# CSI.net
KiCad netlist of a schematic drawn in Altium Designer
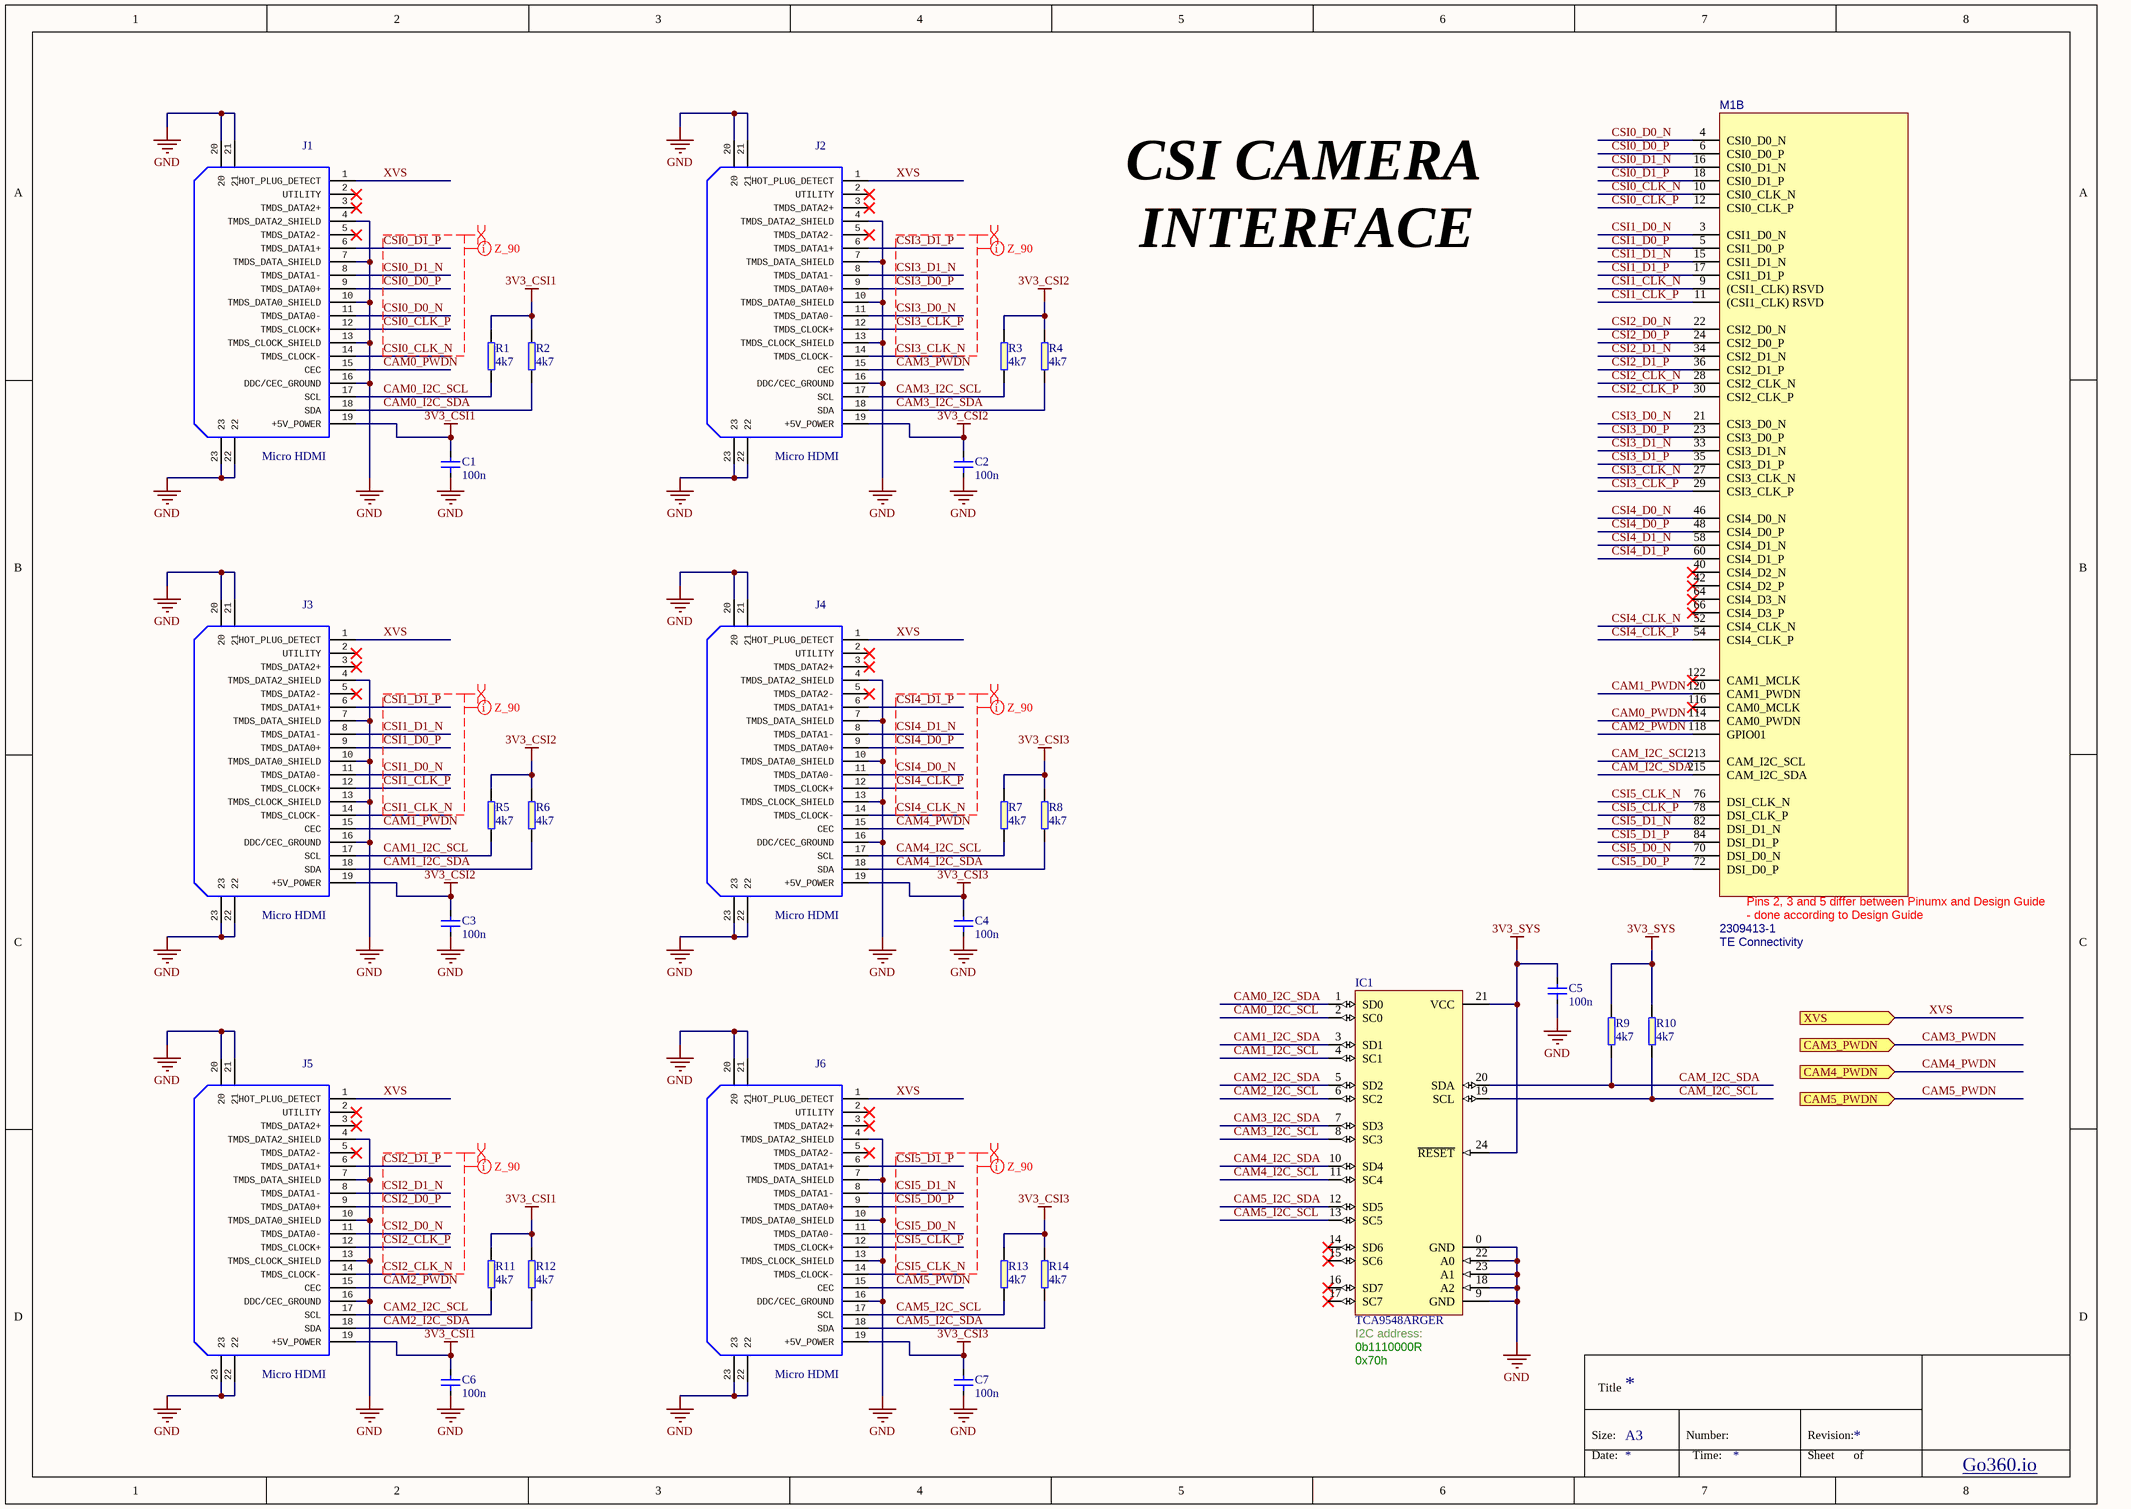
[diagram p0: CSI.SchDoc]

(export (version "E")
  (design (tool "Eeschema 10.0.6"))
  (components
    (comp (ref "C1")
      (value "100n")
      (footprint "C0402")
      (description "MLCC SMT Capacitor 100n 0402")
      (fields (field (name "PARTNUMBER") "C_100n_0402") (field (name "MANUFACTURER") "TDK"))
      (libsource (lib "jetson-nano-baseboard") (part "C_100n_0402"))
    )
    (comp (ref "C2")
      (value "100n")
      (footprint "C0402")
      (description "MLCC SMT Capacitor 100n 0402")
      (fields (field (name "PARTNUMBER") "C_100n_0402") (field (name "MANUFACTURER") "TDK"))
      (libsource (lib "jetson-nano-baseboard") (part "C_100n_0402"))
    )
    (comp (ref "C3")
      (value "100n")
      (footprint "C0402")
      (description "MLCC SMT Capacitor 100n 0402")
      (fields (field (name "PARTNUMBER") "C_100n_0402") (field (name "MANUFACTURER") "TDK"))
      (libsource (lib "jetson-nano-baseboard") (part "C_100n_0402"))
    )
    (comp (ref "C4")
      (value "100n")
      (footprint "C0402")
      (description "MLCC SMT Capacitor 100n 0402")
      (fields (field (name "PARTNUMBER") "C_100n_0402") (field (name "MANUFACTURER") "TDK"))
      (libsource (lib "jetson-nano-baseboard") (part "C_100n_0402"))
    )
    (comp (ref "C5")
      (value "100n")
      (footprint "C0402")
      (description "MLCC SMT Capacitor 100n 0402")
      (fields (field (name "PARTNUMBER") "C_100n_0402") (field (name "MANUFACTURER") "TDK"))
      (libsource (lib "jetson-nano-baseboard") (part "C_100n_0402"))
    )
    (comp (ref "C6")
      (value "100n")
      (footprint "C0402")
      (description "MLCC SMT Capacitor 100n 0402")
      (fields (field (name "PARTNUMBER") "C_100n_0402") (field (name "MANUFACTURER") "TDK"))
      (libsource (lib "jetson-nano-baseboard") (part "C_100n_0402"))
    )
    (comp (ref "C7")
      (value "100n")
      (footprint "C0402")
      (description "MLCC SMT Capacitor 100n 0402")
      (fields (field (name "PARTNUMBER") "C_100n_0402") (field (name "MANUFACTURER") "TDK"))
      (libsource (lib "jetson-nano-baseboard") (part "C_100n_0402"))
    )
    (comp (ref "IC1")
      (value "TCA9548ARGER")
      (footprint "VQFN-24")
      (description "TCA9548ARGER  I2C SWITCH W/ RESET, 8-CH, VQFN-24")
      (fields (field (name "MANUFACTURER") "TEXAS INSTRUMENTS"))
      (libsource (lib "jetson-nano-baseboard") (part "TCA9548A"))
    )
    (comp (ref "J1")
      (value "Micro HDMI")
      (footprint "HDMI-0467650301")
      (libsource (lib "jetson-nano-baseboard") (part "HDMI-0467650301"))
    )
    (comp (ref "J2")
      (value "Micro HDMI")
      (footprint "HDMI-0467650301")
      (libsource (lib "jetson-nano-baseboard") (part "HDMI-0467650301"))
    )
    (comp (ref "J3")
      (value "Micro HDMI")
      (footprint "HDMI-0467650301")
      (libsource (lib "jetson-nano-baseboard") (part "HDMI-0467650301"))
    )
    (comp (ref "J4")
      (value "Micro HDMI")
      (footprint "HDMI-0467650301")
      (libsource (lib "jetson-nano-baseboard") (part "HDMI-0467650301"))
    )
    (comp (ref "J5")
      (value "Micro HDMI")
      (footprint "HDMI-0467650301")
      (libsource (lib "jetson-nano-baseboard") (part "HDMI-0467650301"))
    )
    (comp (ref "J6")
      (value "Micro HDMI")
      (footprint "HDMI-0467650301")
      (libsource (lib "jetson-nano-baseboard") (part "HDMI-0467650301"))
    )
    (comp (ref "M1")
      (value "2309413-1")
      (footprint "jetson-nano-connector")
      (fields (field (name "PARTSYMBOL") "2309413-1") (field (name "MANUFACTURER") "TE Connectivity"))
      (libsource (lib "jetson-nano-baseboard") (part "jetson-nano-new-release"))
    )
    (comp (ref "R1")
      (value "4k7")
      (footprint "R0402")
      (description "RES, 4k7, 0402")
      (fields (field (name "PARTNUMBER") "R_4k7_0402") (field (name "MANUFACTURER") "Panasonic"))
      (libsource (lib "jetson-nano-baseboard") (part "R_4k7_0402"))
    )
    (comp (ref "R2")
      (value "4k7")
      (footprint "R0402")
      (description "RES, 4k7, 0402")
      (fields (field (name "PARTNUMBER") "R_4k7_0402") (field (name "MANUFACTURER") "Panasonic"))
      (libsource (lib "jetson-nano-baseboard") (part "R_4k7_0402"))
    )
    (comp (ref "R3")
      (value "4k7")
      (footprint "R0402")
      (description "RES, 4k7, 0402")
      (fields (field (name "PARTNUMBER") "R_4k7_0402") (field (name "MANUFACTURER") "Panasonic"))
      (libsource (lib "jetson-nano-baseboard") (part "R_4k7_0402"))
    )
    (comp (ref "R4")
      (value "4k7")
      (footprint "R0402")
      (description "RES, 4k7, 0402")
      (fields (field (name "PARTNUMBER") "R_4k7_0402") (field (name "MANUFACTURER") "Panasonic"))
      (libsource (lib "jetson-nano-baseboard") (part "R_4k7_0402"))
    )
    (comp (ref "R5")
      (value "4k7")
      (footprint "R0402")
      (description "RES, 4k7, 0402")
      (fields (field (name "PARTNUMBER") "R_4k7_0402") (field (name "MANUFACTURER") "Panasonic"))
      (libsource (lib "jetson-nano-baseboard") (part "R_4k7_0402"))
    )
    (comp (ref "R6")
      (value "4k7")
      (footprint "R0402")
      (description "RES, 4k7, 0402")
      (fields (field (name "PARTNUMBER") "R_4k7_0402") (field (name "MANUFACTURER") "Panasonic"))
      (libsource (lib "jetson-nano-baseboard") (part "R_4k7_0402"))
    )
    (comp (ref "R7")
      (value "4k7")
      (footprint "R0402")
      (description "RES, 4k7, 0402")
      (fields (field (name "PARTNUMBER") "R_4k7_0402") (field (name "MANUFACTURER") "Panasonic"))
      (libsource (lib "jetson-nano-baseboard") (part "R_4k7_0402"))
    )
    (comp (ref "R8")
      (value "4k7")
      (footprint "R0402")
      (description "RES, 4k7, 0402")
      (fields (field (name "PARTNUMBER") "R_4k7_0402") (field (name "MANUFACTURER") "Panasonic"))
      (libsource (lib "jetson-nano-baseboard") (part "R_4k7_0402"))
    )
    (comp (ref "R9")
      (value "4k7")
      (footprint "R0402")
      (description "RES, 4k7, 0402")
      (fields (field (name "PARTNUMBER") "R_4k7_0402") (field (name "MANUFACTURER") "Panasonic"))
      (libsource (lib "jetson-nano-baseboard") (part "R_4k7_0402"))
    )
    (comp (ref "R10")
      (value "4k7")
      (footprint "R0402")
      (description "RES, 4k7, 0402")
      (fields (field (name "PARTNUMBER") "R_4k7_0402") (field (name "MANUFACTURER") "Panasonic"))
      (libsource (lib "jetson-nano-baseboard") (part "R_4k7_0402"))
    )
    (comp (ref "R11")
      (value "4k7")
      (footprint "R0402")
      (description "RES, 4k7, 0402")
      (fields (field (name "PARTNUMBER") "R_4k7_0402") (field (name "MANUFACTURER") "Panasonic"))
      (libsource (lib "jetson-nano-baseboard") (part "R_4k7_0402"))
    )
    (comp (ref "R12")
      (value "4k7")
      (footprint "R0402")
      (description "RES, 4k7, 0402")
      (fields (field (name "PARTNUMBER") "R_4k7_0402") (field (name "MANUFACTURER") "Panasonic"))
      (libsource (lib "jetson-nano-baseboard") (part "R_4k7_0402"))
    )
    (comp (ref "R13")
      (value "4k7")
      (footprint "R0402")
      (description "RES, 4k7, 0402")
      (fields (field (name "PARTNUMBER") "R_4k7_0402") (field (name "MANUFACTURER") "Panasonic"))
      (libsource (lib "jetson-nano-baseboard") (part "R_4k7_0402"))
    )
    (comp (ref "R14")
      (value "4k7")
      (footprint "R0402")
      (description "RES, 4k7, 0402")
      (fields (field (name "PARTNUMBER") "R_4k7_0402") (field (name "MANUFACTURER") "Panasonic"))
      (libsource (lib "jetson-nano-baseboard") (part "R_4k7_0402"))
    )
  )
  (nets
    (net (code "1") (name "/CAM0_I2C_SCL") (class "Default")
      (node (ref "IC1") (pin "2") (pinfunction "SC0_2") (pintype "bidirectional"))
      (node (ref "J1") (pin "17") (pinfunction "SCL_17") (pintype "passive"))
      (node (ref "R1") (pin "1") (pintype "passive"))
    )
    (net (code "2") (name "/CAM0_I2C_SDA") (class "Default")
      (node (ref "IC1") (pin "1") (pinfunction "SD0_1") (pintype "bidirectional"))
      (node (ref "J1") (pin "18") (pinfunction "SDA_18") (pintype "passive"))
      (node (ref "R2") (pin "1") (pintype "passive"))
    )
    (net (code "3") (name "/CAM0_PWDN") (class "Default")
      (node (ref "J1") (pin "15") (pinfunction "CEC_15") (pintype "passive"))
      (node (ref "M1") (pin "114") (pinfunction "CAM0_PWDN_114") (pintype "passive"))
    )
    (net (code "4") (name "/CAM1_I2C_SCL") (class "Default")
      (node (ref "IC1") (pin "4") (pinfunction "SC1_4") (pintype "bidirectional"))
      (node (ref "J3") (pin "17") (pinfunction "SCL_17") (pintype "passive"))
      (node (ref "R5") (pin "1") (pintype "passive"))
    )
    (net (code "5") (name "/CAM1_I2C_SDA") (class "Default")
      (node (ref "IC1") (pin "3") (pinfunction "SD1_3") (pintype "bidirectional"))
      (node (ref "J3") (pin "18") (pinfunction "SDA_18") (pintype "passive"))
      (node (ref "R6") (pin "1") (pintype "passive"))
    )
    (net (code "6") (name "/CAM1_PWDN") (class "Default")
      (node (ref "J3") (pin "15") (pinfunction "CEC_15") (pintype "passive"))
      (node (ref "M1") (pin "120") (pinfunction "CAM1_PWDN_120") (pintype "passive"))
    )
    (net (code "7") (name "/CAM2_I2C_SCL") (class "Default")
      (node (ref "IC1") (pin "6") (pinfunction "SC2_6") (pintype "bidirectional"))
      (node (ref "J5") (pin "17") (pinfunction "SCL_17") (pintype "passive"))
      (node (ref "R11") (pin "1") (pintype "passive"))
    )
    (net (code "8") (name "/CAM2_I2C_SDA") (class "Default")
      (node (ref "IC1") (pin "5") (pinfunction "SD2_5") (pintype "bidirectional"))
      (node (ref "J5") (pin "18") (pinfunction "SDA_18") (pintype "passive"))
      (node (ref "R12") (pin "1") (pintype "passive"))
    )
    (net (code "9") (name "/CAM2_PWDN") (class "Default")
      (node (ref "J5") (pin "15") (pinfunction "CEC_15") (pintype "passive"))
      (node (ref "M1") (pin "118") (pinfunction "GPIO01_118") (pintype "passive"))
    )
    (net (code "10") (name "/CAM3_I2C_SCL") (class "Default")
      (node (ref "IC1") (pin "8") (pinfunction "SC3_8") (pintype "bidirectional"))
      (node (ref "J2") (pin "17") (pinfunction "SCL_17") (pintype "passive"))
      (node (ref "R3") (pin "1") (pintype "passive"))
    )
    (net (code "11") (name "/CAM3_I2C_SDA") (class "Default")
      (node (ref "IC1") (pin "7") (pinfunction "SD3_7") (pintype "bidirectional"))
      (node (ref "J2") (pin "18") (pinfunction "SDA_18") (pintype "passive"))
      (node (ref "R4") (pin "1") (pintype "passive"))
    )
    (net (code "12") (name "/CAM3_PWDN") (class "Default")
      (node (ref "J2") (pin "15") (pinfunction "CEC_15") (pintype "passive"))
    )
    (net (code "13") (name "/CAM4_I2C_SCL") (class "Default")
      (node (ref "IC1") (pin "11") (pinfunction "SC4_11") (pintype "bidirectional"))
      (node (ref "J4") (pin "17") (pinfunction "SCL_17") (pintype "passive"))
      (node (ref "R7") (pin "1") (pintype "passive"))
    )
    (net (code "14") (name "/CAM4_I2C_SDA") (class "Default")
      (node (ref "IC1") (pin "10") (pinfunction "SD4_10") (pintype "bidirectional"))
      (node (ref "J4") (pin "18") (pinfunction "SDA_18") (pintype "passive"))
      (node (ref "R8") (pin "1") (pintype "passive"))
    )
    (net (code "15") (name "/CAM4_PWDN") (class "Default")
      (node (ref "J4") (pin "15") (pinfunction "CEC_15") (pintype "passive"))
    )
    (net (code "16") (name "/CAM5_I2C_SCL") (class "Default")
      (node (ref "IC1") (pin "13") (pinfunction "SC5_13") (pintype "bidirectional"))
      (node (ref "J6") (pin "17") (pinfunction "SCL_17") (pintype "passive"))
      (node (ref "R13") (pin "1") (pintype "passive"))
    )
    (net (code "17") (name "/CAM5_I2C_SDA") (class "Default")
      (node (ref "IC1") (pin "12") (pinfunction "SD5_12") (pintype "bidirectional"))
      (node (ref "J6") (pin "18") (pinfunction "SDA_18") (pintype "passive"))
      (node (ref "R14") (pin "1") (pintype "passive"))
    )
    (net (code "18") (name "/CAM5_PWDN") (class "Default")
      (node (ref "J6") (pin "15") (pinfunction "CEC_15") (pintype "passive"))
    )
    (net (code "19") (name "/CAM_I2C_SCL") (class "Default")
      (node (ref "IC1") (pin "19") (pinfunction "SCL_19") (pintype "bidirectional"))
      (node (ref "M1") (pin "213") (pinfunction "CAM_I2C_SCL_213") (pintype "passive"))
      (node (ref "R10") (pin "1") (pintype "passive"))
    )
    (net (code "20") (name "/CAM_I2C_SDA") (class "Default")
      (node (ref "IC1") (pin "20") (pinfunction "SDA_20") (pintype "bidirectional"))
      (node (ref "M1") (pin "215") (pinfunction "CAM_I2C_SDA_215") (pintype "passive"))
      (node (ref "R9") (pin "1") (pintype "passive"))
    )
    (net (code "21") (name "/CSI0_CLK_N") (class "Default")
      (node (ref "J1") (pin "14") (pinfunction "TMDS_CLOCK-_14") (pintype "passive"))
      (node (ref "M1") (pin "10") (pinfunction "CSI0_CLK_N_10") (pintype "passive"))
    )
    (net (code "22") (name "/CSI0_CLK_P") (class "Default")
      (node (ref "J1") (pin "12") (pinfunction "TMDS_CLOCK+_12") (pintype "passive"))
      (node (ref "M1") (pin "12") (pinfunction "CSI0_CLK_P_12") (pintype "passive"))
    )
    (net (code "23") (name "/CSI0_D0_N") (class "Default")
      (node (ref "J1") (pin "11") (pinfunction "TMDS_DATA0-_11") (pintype "passive"))
      (node (ref "M1") (pin "4") (pinfunction "CSI0_D0_N_4") (pintype "passive"))
    )
    (net (code "24") (name "/CSI0_D0_P") (class "Default")
      (node (ref "J1") (pin "9") (pinfunction "TMDS_DATA0+_9") (pintype "passive"))
      (node (ref "M1") (pin "6") (pinfunction "CSI0_D0_P_6") (pintype "passive"))
    )
    (net (code "25") (name "/CSI0_D1_N") (class "Default")
      (node (ref "J1") (pin "8") (pinfunction "TMDS_DATA1-_8") (pintype "passive"))
      (node (ref "M1") (pin "16") (pinfunction "CSI0_D1_N_16") (pintype "passive"))
    )
    (net (code "26") (name "/CSI0_D1_P") (class "Default")
      (node (ref "J1") (pin "6") (pinfunction "TMDS_DATA1+_6") (pintype "passive"))
      (node (ref "M1") (pin "18") (pinfunction "CSI0_D1_P_18") (pintype "passive"))
    )
    (net (code "27") (name "/CSI1_CLK_N") (class "Default")
      (node (ref "J3") (pin "14") (pinfunction "TMDS_CLOCK-_14") (pintype "passive"))
      (node (ref "M1") (pin "9") (pinfunction "(CSI1_CLK)_RSVD_9") (pintype "passive"))
    )
    (net (code "28") (name "/CSI1_CLK_P") (class "Default")
      (node (ref "J3") (pin "12") (pinfunction "TMDS_CLOCK+_12") (pintype "passive"))
      (node (ref "M1") (pin "11") (pinfunction "(CSI1_CLK)_RSVD_11") (pintype "passive"))
    )
    (net (code "29") (name "/CSI1_D0_N") (class "Default")
      (node (ref "J3") (pin "11") (pinfunction "TMDS_DATA0-_11") (pintype "passive"))
      (node (ref "M1") (pin "3") (pinfunction "CSI1_D0_N_3") (pintype "passive"))
    )
    (net (code "30") (name "/CSI1_D0_P") (class "Default")
      (node (ref "J3") (pin "9") (pinfunction "TMDS_DATA0+_9") (pintype "passive"))
      (node (ref "M1") (pin "5") (pinfunction "CSI1_D0_P_5") (pintype "passive"))
    )
    (net (code "31") (name "/CSI1_D1_N") (class "Default")
      (node (ref "J3") (pin "8") (pinfunction "TMDS_DATA1-_8") (pintype "passive"))
      (node (ref "M1") (pin "15") (pinfunction "CSI1_D1_N_15") (pintype "passive"))
    )
    (net (code "32") (name "/CSI1_D1_P") (class "Default")
      (node (ref "J3") (pin "6") (pinfunction "TMDS_DATA1+_6") (pintype "passive"))
      (node (ref "M1") (pin "17") (pinfunction "CSI1_D1_P_17") (pintype "passive"))
    )
    (net (code "33") (name "/CSI2_CLK_N") (class "Default")
      (node (ref "J5") (pin "14") (pinfunction "TMDS_CLOCK-_14") (pintype "passive"))
      (node (ref "M1") (pin "28") (pinfunction "CSI2_CLK_N_28") (pintype "passive"))
    )
    (net (code "34") (name "/CSI2_CLK_P") (class "Default")
      (node (ref "J5") (pin "12") (pinfunction "TMDS_CLOCK+_12") (pintype "passive"))
      (node (ref "M1") (pin "30") (pinfunction "CSI2_CLK_P_30") (pintype "passive"))
    )
    (net (code "35") (name "/CSI2_D0_N") (class "Default")
      (node (ref "J5") (pin "11") (pinfunction "TMDS_DATA0-_11") (pintype "passive"))
      (node (ref "M1") (pin "22") (pinfunction "CSI2_D0_N_22") (pintype "passive"))
    )
    (net (code "36") (name "/CSI2_D0_P") (class "Default")
      (node (ref "J5") (pin "9") (pinfunction "TMDS_DATA0+_9") (pintype "passive"))
      (node (ref "M1") (pin "24") (pinfunction "CSI2_D0_P_24") (pintype "passive"))
    )
    (net (code "37") (name "/CSI2_D1_N") (class "Default")
      (node (ref "J5") (pin "8") (pinfunction "TMDS_DATA1-_8") (pintype "passive"))
      (node (ref "M1") (pin "34") (pinfunction "CSI2_D1_N_34") (pintype "passive"))
    )
    (net (code "38") (name "/CSI2_D1_P") (class "Default")
      (node (ref "J5") (pin "6") (pinfunction "TMDS_DATA1+_6") (pintype "passive"))
      (node (ref "M1") (pin "36") (pinfunction "CSI2_D1_P_36") (pintype "passive"))
    )
    (net (code "39") (name "/CSI3_CLK_N") (class "Default")
      (node (ref "J2") (pin "14") (pinfunction "TMDS_CLOCK-_14") (pintype "passive"))
      (node (ref "M1") (pin "27") (pinfunction "CSI3_CLK_N_27") (pintype "passive"))
    )
    (net (code "40") (name "/CSI3_CLK_P") (class "Default")
      (node (ref "J2") (pin "12") (pinfunction "TMDS_CLOCK+_12") (pintype "passive"))
      (node (ref "M1") (pin "29") (pinfunction "CSI3_CLK_P_29") (pintype "passive"))
    )
    (net (code "41") (name "/CSI3_D0_N") (class "Default")
      (node (ref "J2") (pin "11") (pinfunction "TMDS_DATA0-_11") (pintype "passive"))
      (node (ref "M1") (pin "21") (pinfunction "CSI3_D0_N_21") (pintype "passive"))
    )
    (net (code "42") (name "/CSI3_D0_P") (class "Default")
      (node (ref "J2") (pin "9") (pinfunction "TMDS_DATA0+_9") (pintype "passive"))
      (node (ref "M1") (pin "23") (pinfunction "CSI3_D0_P_23") (pintype "passive"))
    )
    (net (code "43") (name "/CSI3_D1_N") (class "Default")
      (node (ref "J2") (pin "8") (pinfunction "TMDS_DATA1-_8") (pintype "passive"))
      (node (ref "M1") (pin "33") (pinfunction "CSI3_D1_N_33") (pintype "passive"))
    )
    (net (code "44") (name "/CSI3_D1_P") (class "Default")
      (node (ref "J2") (pin "6") (pinfunction "TMDS_DATA1+_6") (pintype "passive"))
      (node (ref "M1") (pin "35") (pinfunction "CSI3_D1_P_35") (pintype "passive"))
    )
    (net (code "45") (name "/CSI4_CLK_N") (class "Default")
      (node (ref "J4") (pin "14") (pinfunction "TMDS_CLOCK-_14") (pintype "passive"))
      (node (ref "M1") (pin "52") (pinfunction "CSI4_CLK_N_52") (pintype "passive"))
    )
    (net (code "46") (name "/CSI4_CLK_P") (class "Default")
      (node (ref "J4") (pin "12") (pinfunction "TMDS_CLOCK+_12") (pintype "passive"))
      (node (ref "M1") (pin "54") (pinfunction "CSI4_CLK_P_54") (pintype "passive"))
    )
    (net (code "47") (name "/CSI4_D0_N") (class "Default")
      (node (ref "J4") (pin "11") (pinfunction "TMDS_DATA0-_11") (pintype "passive"))
      (node (ref "M1") (pin "46") (pinfunction "CSI4_D0_N_46") (pintype "passive"))
    )
    (net (code "48") (name "/CSI4_D0_P") (class "Default")
      (node (ref "J4") (pin "9") (pinfunction "TMDS_DATA0+_9") (pintype "passive"))
      (node (ref "M1") (pin "48") (pinfunction "CSI4_D0_P_48") (pintype "passive"))
    )
    (net (code "49") (name "/CSI4_D1_N") (class "Default")
      (node (ref "J4") (pin "8") (pinfunction "TMDS_DATA1-_8") (pintype "passive"))
      (node (ref "M1") (pin "58") (pinfunction "CSI4_D1_N_58") (pintype "passive"))
    )
    (net (code "50") (name "/CSI4_D1_P") (class "Default")
      (node (ref "J4") (pin "6") (pinfunction "TMDS_DATA1+_6") (pintype "passive"))
      (node (ref "M1") (pin "60") (pinfunction "CSI4_D1_P_60") (pintype "passive"))
    )
    (net (code "51") (name "/CSI5_CLK_N") (class "Default")
      (node (ref "J6") (pin "14") (pinfunction "TMDS_CLOCK-_14") (pintype "passive"))
      (node (ref "M1") (pin "76") (pinfunction "DSI_CLK_N_76") (pintype "passive"))
    )
    (net (code "52") (name "/CSI5_CLK_P") (class "Default")
      (node (ref "J6") (pin "12") (pinfunction "TMDS_CLOCK+_12") (pintype "passive"))
      (node (ref "M1") (pin "78") (pinfunction "DSI_CLK_P_78") (pintype "passive"))
    )
    (net (code "53") (name "/CSI5_D0_N") (class "Default")
      (node (ref "J6") (pin "11") (pinfunction "TMDS_DATA0-_11") (pintype "passive"))
      (node (ref "M1") (pin "70") (pinfunction "DSI_D0_N_70") (pintype "passive"))
    )
    (net (code "54") (name "/CSI5_D0_P") (class "Default")
      (node (ref "J6") (pin "9") (pinfunction "TMDS_DATA0+_9") (pintype "passive"))
      (node (ref "M1") (pin "72") (pinfunction "DSI_D0_P_72") (pintype "passive"))
    )
    (net (code "55") (name "/CSI5_D1_N") (class "Default")
      (node (ref "J6") (pin "8") (pinfunction "TMDS_DATA1-_8") (pintype "passive"))
      (node (ref "M1") (pin "82") (pinfunction "DSI_D1_N_82") (pintype "passive"))
    )
    (net (code "56") (name "/CSI5_D1_P") (class "Default")
      (node (ref "J6") (pin "6") (pinfunction "TMDS_DATA1+_6") (pintype "passive"))
      (node (ref "M1") (pin "84") (pinfunction "DSI_D1_P_84") (pintype "passive"))
    )
    (net (code "57") (name "/XVS") (class "Default")
      (node (ref "J1") (pin "1") (pinfunction "HOT_PLUG_DETECT_1") (pintype "passive"))
      (node (ref "J2") (pin "1") (pinfunction "HOT_PLUG_DETECT_1") (pintype "passive"))
      (node (ref "J3") (pin "1") (pinfunction "HOT_PLUG_DETECT_1") (pintype "passive"))
      (node (ref "J4") (pin "1") (pinfunction "HOT_PLUG_DETECT_1") (pintype "passive"))
      (node (ref "J5") (pin "1") (pinfunction "HOT_PLUG_DETECT_1") (pintype "passive"))
      (node (ref "J6") (pin "1") (pinfunction "HOT_PLUG_DETECT_1") (pintype "passive"))
    )
    (net (code "58") (name "3V3_CSI1") (class "Default")
      (node (ref "C1") (pin "2") (pinfunction "2_2") (pintype "passive"))
      (node (ref "C6") (pin "2") (pinfunction "2_2") (pintype "passive"))
      (node (ref "J1") (pin "19") (pinfunction "+5V_POWER_19") (pintype "passive"))
      (node (ref "J5") (pin "19") (pinfunction "+5V_POWER_19") (pintype "passive"))
      (node (ref "R1") (pin "2") (pintype "passive"))
      (node (ref "R11") (pin "2") (pintype "passive"))
      (node (ref "R12") (pin "2") (pintype "passive"))
      (node (ref "R2") (pin "2") (pintype "passive"))
    )
    (net (code "59") (name "3V3_CSI2") (class "Default")
      (node (ref "C2") (pin "2") (pinfunction "2_2") (pintype "passive"))
      (node (ref "C3") (pin "2") (pinfunction "2_2") (pintype "passive"))
      (node (ref "J2") (pin "19") (pinfunction "+5V_POWER_19") (pintype "passive"))
      (node (ref "J3") (pin "19") (pinfunction "+5V_POWER_19") (pintype "passive"))
      (node (ref "R3") (pin "2") (pintype "passive"))
      (node (ref "R4") (pin "2") (pintype "passive"))
      (node (ref "R5") (pin "2") (pintype "passive"))
      (node (ref "R6") (pin "2") (pintype "passive"))
    )
    (net (code "60") (name "3V3_CSI3") (class "Default")
      (node (ref "C4") (pin "2") (pinfunction "2_2") (pintype "passive"))
      (node (ref "C7") (pin "2") (pinfunction "2_2") (pintype "passive"))
      (node (ref "J4") (pin "19") (pinfunction "+5V_POWER_19") (pintype "passive"))
      (node (ref "J6") (pin "19") (pinfunction "+5V_POWER_19") (pintype "passive"))
      (node (ref "R13") (pin "2") (pintype "passive"))
      (node (ref "R14") (pin "2") (pintype "passive"))
      (node (ref "R7") (pin "2") (pintype "passive"))
      (node (ref "R8") (pin "2") (pintype "passive"))
    )
    (net (code "61") (name "3V3_SYS") (class "Default")
      (node (ref "C5") (pin "2") (pinfunction "2_2") (pintype "passive"))
      (node (ref "IC1") (pin "21") (pinfunction "VCC_21") (pintype "power_in"))
      (node (ref "IC1") (pin "24") (pinfunction "~{RESET}_24") (pintype "input"))
      (node (ref "R10") (pin "2") (pintype "passive"))
      (node (ref "R9") (pin "2") (pintype "passive"))
    )
    (net (code "62") (name "GND") (class "Default")
      (node (ref "C1") (pin "1") (pinfunction "1_1") (pintype "passive"))
      (node (ref "C2") (pin "1") (pinfunction "1_1") (pintype "passive"))
      (node (ref "C3") (pin "1") (pinfunction "1_1") (pintype "passive"))
      (node (ref "C4") (pin "1") (pinfunction "1_1") (pintype "passive"))
      (node (ref "C5") (pin "1") (pinfunction "1_1") (pintype "passive"))
      (node (ref "C6") (pin "1") (pinfunction "1_1") (pintype "passive"))
      (node (ref "C7") (pin "1") (pinfunction "1_1") (pintype "passive"))
      (node (ref "IC1") (pin "0") (pinfunction "GND_0") (pintype "power_in"))
      (node (ref "IC1") (pin "18") (pinfunction "A2_18") (pintype "input"))
      (node (ref "IC1") (pin "22") (pinfunction "A0_22") (pintype "input"))
      (node (ref "IC1") (pin "23") (pinfunction "A1_23") (pintype "input"))
      (node (ref "IC1") (pin "9") (pinfunction "GND_9") (pintype "power_in"))
      (node (ref "J1") (pin "10") (pinfunction "TMDS_DATA0_SHIELD_10") (pintype "passive"))
      (node (ref "J1") (pin "13") (pinfunction "TMDS_CLOCK_SHIELD_13") (pintype "passive"))
      (node (ref "J1") (pin "16") (pinfunction "DDC/CEC_GROUND_16") (pintype "passive"))
      (node (ref "J1") (pin "20") (pinfunction "20_20") (pintype "passive"))
      (node (ref "J1") (pin "21") (pinfunction "21_21") (pintype "passive"))
      (node (ref "J1") (pin "22") (pinfunction "22_22") (pintype "passive"))
      (node (ref "J1") (pin "23") (pinfunction "23_23") (pintype "passive"))
      (node (ref "J1") (pin "4") (pinfunction "TMDS_DATA2_SHIELD_4") (pintype "passive"))
      (node (ref "J1") (pin "7") (pinfunction "TMDS_DATA_SHIELD_7") (pintype "passive"))
      (node (ref "J2") (pin "10") (pinfunction "TMDS_DATA0_SHIELD_10") (pintype "passive"))
      (node (ref "J2") (pin "13") (pinfunction "TMDS_CLOCK_SHIELD_13") (pintype "passive"))
      (node (ref "J2") (pin "16") (pinfunction "DDC/CEC_GROUND_16") (pintype "passive"))
      (node (ref "J2") (pin "20") (pinfunction "20_20") (pintype "passive"))
      (node (ref "J2") (pin "21") (pinfunction "21_21") (pintype "passive"))
      (node (ref "J2") (pin "22") (pinfunction "22_22") (pintype "passive"))
      (node (ref "J2") (pin "23") (pinfunction "23_23") (pintype "passive"))
      (node (ref "J2") (pin "4") (pinfunction "TMDS_DATA2_SHIELD_4") (pintype "passive"))
      (node (ref "J2") (pin "7") (pinfunction "TMDS_DATA_SHIELD_7") (pintype "passive"))
      (node (ref "J3") (pin "10") (pinfunction "TMDS_DATA0_SHIELD_10") (pintype "passive"))
      (node (ref "J3") (pin "13") (pinfunction "TMDS_CLOCK_SHIELD_13") (pintype "passive"))
      (node (ref "J3") (pin "16") (pinfunction "DDC/CEC_GROUND_16") (pintype "passive"))
      (node (ref "J3") (pin "20") (pinfunction "20_20") (pintype "passive"))
      (node (ref "J3") (pin "21") (pinfunction "21_21") (pintype "passive"))
      (node (ref "J3") (pin "22") (pinfunction "22_22") (pintype "passive"))
      (node (ref "J3") (pin "23") (pinfunction "23_23") (pintype "passive"))
      (node (ref "J3") (pin "4") (pinfunction "TMDS_DATA2_SHIELD_4") (pintype "passive"))
      (node (ref "J3") (pin "7") (pinfunction "TMDS_DATA_SHIELD_7") (pintype "passive"))
      (node (ref "J4") (pin "10") (pinfunction "TMDS_DATA0_SHIELD_10") (pintype "passive"))
      (node (ref "J4") (pin "13") (pinfunction "TMDS_CLOCK_SHIELD_13") (pintype "passive"))
      (node (ref "J4") (pin "16") (pinfunction "DDC/CEC_GROUND_16") (pintype "passive"))
      (node (ref "J4") (pin "20") (pinfunction "20_20") (pintype "passive"))
      (node (ref "J4") (pin "21") (pinfunction "21_21") (pintype "passive"))
      (node (ref "J4") (pin "22") (pinfunction "22_22") (pintype "passive"))
      (node (ref "J4") (pin "23") (pinfunction "23_23") (pintype "passive"))
      (node (ref "J4") (pin "4") (pinfunction "TMDS_DATA2_SHIELD_4") (pintype "passive"))
      (node (ref "J4") (pin "7") (pinfunction "TMDS_DATA_SHIELD_7") (pintype "passive"))
      (node (ref "J5") (pin "10") (pinfunction "TMDS_DATA0_SHIELD_10") (pintype "passive"))
      (node (ref "J5") (pin "13") (pinfunction "TMDS_CLOCK_SHIELD_13") (pintype "passive"))
      (node (ref "J5") (pin "16") (pinfunction "DDC/CEC_GROUND_16") (pintype "passive"))
      (node (ref "J5") (pin "20") (pinfunction "20_20") (pintype "passive"))
      (node (ref "J5") (pin "21") (pinfunction "21_21") (pintype "passive"))
      (node (ref "J5") (pin "22") (pinfunction "22_22") (pintype "passive"))
      (node (ref "J5") (pin "23") (pinfunction "23_23") (pintype "passive"))
      (node (ref "J5") (pin "4") (pinfunction "TMDS_DATA2_SHIELD_4") (pintype "passive"))
      (node (ref "J5") (pin "7") (pinfunction "TMDS_DATA_SHIELD_7") (pintype "passive"))
      (node (ref "J6") (pin "10") (pinfunction "TMDS_DATA0_SHIELD_10") (pintype "passive"))
      (node (ref "J6") (pin "13") (pinfunction "TMDS_CLOCK_SHIELD_13") (pintype "passive"))
      (node (ref "J6") (pin "16") (pinfunction "DDC/CEC_GROUND_16") (pintype "passive"))
      (node (ref "J6") (pin "20") (pinfunction "20_20") (pintype "passive"))
      (node (ref "J6") (pin "21") (pinfunction "21_21") (pintype "passive"))
      (node (ref "J6") (pin "22") (pinfunction "22_22") (pintype "passive"))
      (node (ref "J6") (pin "23") (pinfunction "23_23") (pintype "passive"))
      (node (ref "J6") (pin "4") (pinfunction "TMDS_DATA2_SHIELD_4") (pintype "passive"))
      (node (ref "J6") (pin "7") (pinfunction "TMDS_DATA_SHIELD_7") (pintype "passive"))
    )
    (net (code "63") (name "unconnected-(IC1-SC6-Pad15)") (class "Default")
      (node (ref "IC1") (pin "15") (pinfunction "SC6_15") (pintype "bidirectional+no_connect"))
    )
    (net (code "64") (name "unconnected-(IC1-SC7-Pad17)") (class "Default")
      (node (ref "IC1") (pin "17") (pinfunction "SC7_17") (pintype "bidirectional+no_connect"))
    )
    (net (code "65") (name "unconnected-(IC1-SD6-Pad14)") (class "Default")
      (node (ref "IC1") (pin "14") (pinfunction "SD6_14") (pintype "bidirectional+no_connect"))
    )
    (net (code "66") (name "unconnected-(IC1-SD7-Pad16)") (class "Default")
      (node (ref "IC1") (pin "16") (pinfunction "SD7_16") (pintype "bidirectional+no_connect"))
    )
    (net (code "67") (name "unconnected-(J1-TMDS_DATA2+-Pad3)") (class "Default")
      (node (ref "J1") (pin "3") (pinfunction "TMDS_DATA2+_3") (pintype "passive+no_connect"))
    )
    (net (code "68") (name "unconnected-(J1-TMDS_DATA2--Pad5)") (class "Default")
      (node (ref "J1") (pin "5") (pinfunction "TMDS_DATA2-_5") (pintype "passive+no_connect"))
    )
    (net (code "69") (name "unconnected-(J1-UTILITY-Pad2)") (class "Default")
      (node (ref "J1") (pin "2") (pinfunction "UTILITY_2") (pintype "passive+no_connect"))
    )
    (net (code "70") (name "unconnected-(J2-TMDS_DATA2+-Pad3)") (class "Default")
      (node (ref "J2") (pin "3") (pinfunction "TMDS_DATA2+_3") (pintype "passive+no_connect"))
    )
    (net (code "71") (name "unconnected-(J2-TMDS_DATA2--Pad5)") (class "Default")
      (node (ref "J2") (pin "5") (pinfunction "TMDS_DATA2-_5") (pintype "passive+no_connect"))
    )
    (net (code "72") (name "unconnected-(J2-UTILITY-Pad2)") (class "Default")
      (node (ref "J2") (pin "2") (pinfunction "UTILITY_2") (pintype "passive+no_connect"))
    )
    (net (code "73") (name "unconnected-(J3-TMDS_DATA2+-Pad3)") (class "Default")
      (node (ref "J3") (pin "3") (pinfunction "TMDS_DATA2+_3") (pintype "passive+no_connect"))
    )
    (net (code "74") (name "unconnected-(J3-TMDS_DATA2--Pad5)") (class "Default")
      (node (ref "J3") (pin "5") (pinfunction "TMDS_DATA2-_5") (pintype "passive+no_connect"))
    )
    (net (code "75") (name "unconnected-(J3-UTILITY-Pad2)") (class "Default")
      (node (ref "J3") (pin "2") (pinfunction "UTILITY_2") (pintype "passive+no_connect"))
    )
    (net (code "76") (name "unconnected-(J4-TMDS_DATA2+-Pad3)") (class "Default")
      (node (ref "J4") (pin "3") (pinfunction "TMDS_DATA2+_3") (pintype "passive+no_connect"))
    )
    (net (code "77") (name "unconnected-(J4-TMDS_DATA2--Pad5)") (class "Default")
      (node (ref "J4") (pin "5") (pinfunction "TMDS_DATA2-_5") (pintype "passive+no_connect"))
    )
    (net (code "78") (name "unconnected-(J4-UTILITY-Pad2)") (class "Default")
      (node (ref "J4") (pin "2") (pinfunction "UTILITY_2") (pintype "passive+no_connect"))
    )
    (net (code "79") (name "unconnected-(J5-TMDS_DATA2+-Pad3)") (class "Default")
      (node (ref "J5") (pin "3") (pinfunction "TMDS_DATA2+_3") (pintype "passive+no_connect"))
    )
    (net (code "80") (name "unconnected-(J5-TMDS_DATA2--Pad5)") (class "Default")
      (node (ref "J5") (pin "5") (pinfunction "TMDS_DATA2-_5") (pintype "passive+no_connect"))
    )
    (net (code "81") (name "unconnected-(J5-UTILITY-Pad2)") (class "Default")
      (node (ref "J5") (pin "2") (pinfunction "UTILITY_2") (pintype "passive+no_connect"))
    )
    (net (code "82") (name "unconnected-(J6-TMDS_DATA2+-Pad3)") (class "Default")
      (node (ref "J6") (pin "3") (pinfunction "TMDS_DATA2+_3") (pintype "passive+no_connect"))
    )
    (net (code "83") (name "unconnected-(J6-TMDS_DATA2--Pad5)") (class "Default")
      (node (ref "J6") (pin "5") (pinfunction "TMDS_DATA2-_5") (pintype "passive+no_connect"))
    )
    (net (code "84") (name "unconnected-(J6-UTILITY-Pad2)") (class "Default")
      (node (ref "J6") (pin "2") (pinfunction "UTILITY_2") (pintype "passive+no_connect"))
    )
    (net (code "85") (name "unconnected-(M1B-CAM0_MCLK-Pad116)") (class "Default")
      (node (ref "M1") (pin "116") (pinfunction "CAM0_MCLK_116") (pintype "passive+no_connect"))
    )
    (net (code "86") (name "unconnected-(M1B-CAM1_MCLK-Pad122)") (class "Default")
      (node (ref "M1") (pin "122") (pinfunction "CAM1_MCLK_122") (pintype "passive+no_connect"))
    )
    (net (code "87") (name "unconnected-(M1B-CSI4_D2_N-Pad40)") (class "Default")
      (node (ref "M1") (pin "40") (pinfunction "CSI4_D2_N_40") (pintype "passive+no_connect"))
    )
    (net (code "88") (name "unconnected-(M1B-CSI4_D2_P-Pad42)") (class "Default")
      (node (ref "M1") (pin "42") (pinfunction "CSI4_D2_P_42") (pintype "passive+no_connect"))
    )
    (net (code "89") (name "unconnected-(M1B-CSI4_D3_N-Pad64)") (class "Default")
      (node (ref "M1") (pin "64") (pinfunction "CSI4_D3_N_64") (pintype "passive+no_connect"))
    )
    (net (code "90") (name "unconnected-(M1B-CSI4_D3_P-Pad66)") (class "Default")
      (node (ref "M1") (pin "66") (pinfunction "CSI4_D3_P_66") (pintype "passive+no_connect"))
    )
  )
)
